# LeftSensor.net
KiCad netlist of a schematic drawn in EAGLE
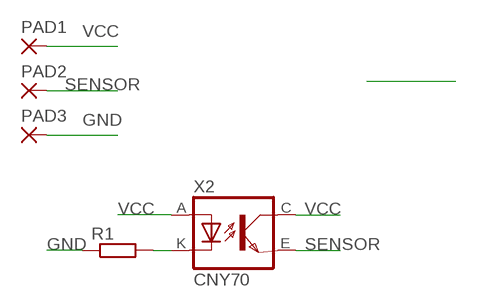
[diagram p0: schematic, sheet 1]

(export (version "E")
  (design (tool "Eeschema 10.0.6"))
  (components
    (comp (ref "PAD1")
      (value "WIREPADSMD1,27-254")
      (footprint "eagle-import:SMD1,27-2,54")
      (libsource (lib "eagle-import") (part "wirepad_412_WIREPADSMD1,27-254"))
    )
    (comp (ref "PAD2")
      (value "WIREPADSMD1,27-254")
      (footprint "eagle-import:SMD1,27-2,54")
      (libsource (lib "eagle-import") (part "WIREPADSMD1,27-254"))
    )
    (comp (ref "PAD3")
      (value "WIREPADSMD1,27-254")
      (footprint "eagle-import:SMD1,27-2,54")
      (libsource (lib "eagle-import") (part "WIREPADSMD1,27-254"))
    )
    (comp (ref "R1")
      (value "RCL_R-EU_R0805")
      (footprint "eagle-import:RCL_R0805")
      (libsource (lib "eagle-import") (part "RCL_R-EU_R0805"))
    )
    (comp (ref "X2")
      (value "CNY70")
      (footprint "eagle-import:4")
      (libsource (lib "eagle-import") (part "CNY70"))
    )
  )
  (nets
    (net (code "1") (name "/GND") (class "Default")
      (node (ref "PAD3") (pin "1") (pinfunction "P_1") (pintype "passive"))
      (node (ref "R1") (pin "1") (pinfunction "1_1") (pintype "passive"))
    )
    (net (code "2") (name "/SENSOR") (class "Default")
      (node (ref "PAD2") (pin "1") (pinfunction "P_1") (pintype "passive"))
      (node (ref "X2") (pin "E") (pinfunction "EMI_E") (pintype "passive"))
    )
    (net (code "3") (name "/VCC") (class "Default")
      (node (ref "PAD1") (pin "1") (pinfunction "P_1") (pintype "passive"))
      (node (ref "X2") (pin "A") (pinfunction "A_A") (pintype "passive"))
      (node (ref "X2") (pin "C") (pinfunction "COL_C") (pintype "passive"))
    )
    (net (code "4") (name "Net-(X2-C)") (class "Default")
      (node (ref "R1") (pin "2") (pinfunction "2_2") (pintype "passive"))
      (node (ref "X2") (pin "K") (pinfunction "C_K") (pintype "passive"))
    )
  )
)
